# dartBoardATMEGAV1.net
KiCad netlist of a schematic drawn in EAGLE
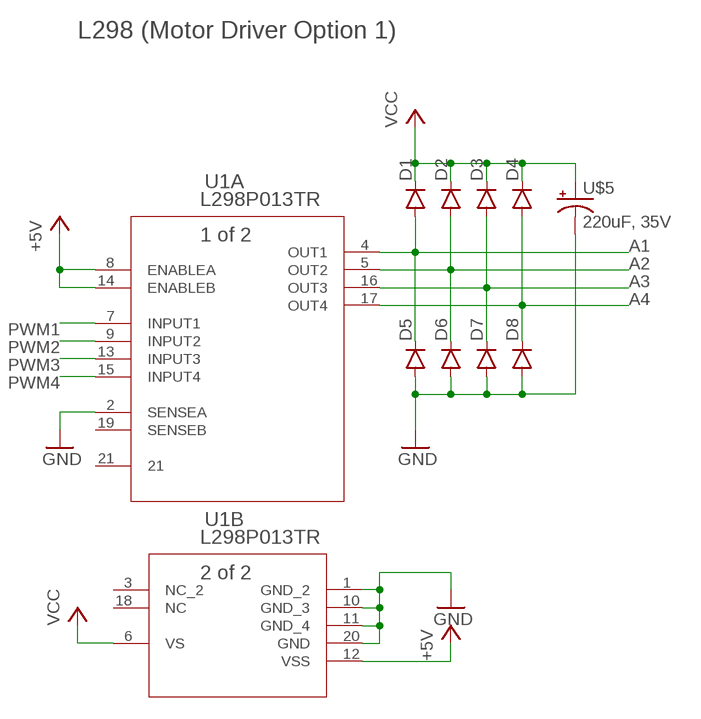
[diagram p0: schematic, sheet 1, part 1 of 2]
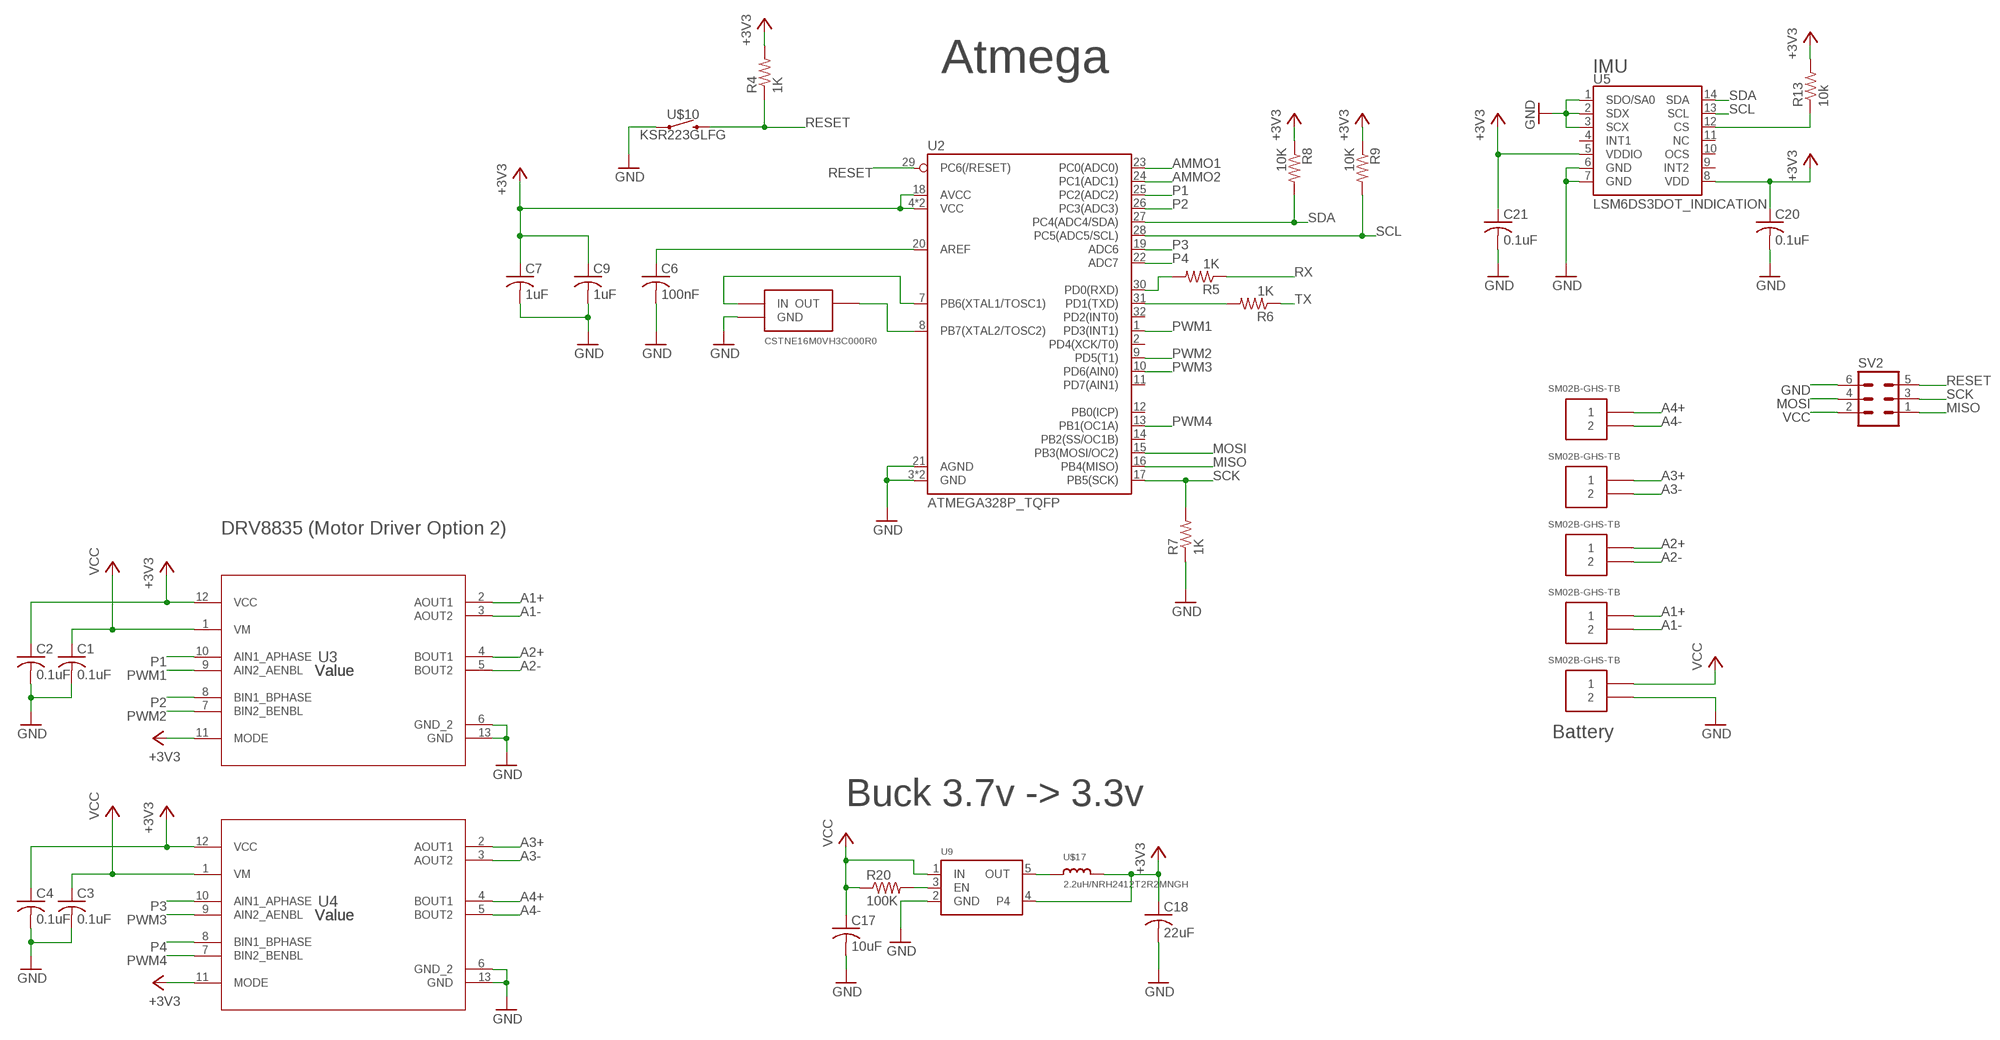
[diagram p1: schematic, sheet 1, part 2 of 2]

(export (version "E")
  (design (tool "Eeschema 10.0.6"))
  (components
    (comp (ref "C1")
      (value "0.1uF")
      (footprint "eagle-import:C0603")
      (libsource (lib "eagle-import") (part "C-USC0603"))
    )
    (comp (ref "C2")
      (value "0.1uF")
      (footprint "eagle-import:C0603")
      (libsource (lib "eagle-import") (part "C-USC0603"))
    )
    (comp (ref "C3")
      (value "0.1uF")
      (footprint "eagle-import:C0603")
      (libsource (lib "eagle-import") (part "C-USC0603"))
    )
    (comp (ref "C4")
      (value "0.1uF")
      (footprint "eagle-import:C0603")
      (libsource (lib "eagle-import") (part "C-USC0603"))
    )
    (comp (ref "C6")
      (value "100nF")
      (footprint "eagle-import:C0603")
      (libsource (lib "eagle-import") (part "C-USC0603"))
    )
    (comp (ref "C7")
      (value "1uF")
      (footprint "eagle-import:C0603")
      (libsource (lib "eagle-import") (part "C-USC0603"))
    )
    (comp (ref "C9")
      (value "1uF")
      (footprint "eagle-import:C0603")
      (libsource (lib "eagle-import") (part "C-USC0603"))
    )
    (comp (ref "C17")
      (value "10uF")
      (footprint "eagle-import:C0603")
      (libsource (lib "eagle-import") (part "C-USC0603"))
    )
    (comp (ref "C18")
      (value "22uF")
      (footprint "eagle-import:C0603")
      (libsource (lib "eagle-import") (part "C-USC0603"))
    )
    (comp (ref "C20")
      (value "0.1uF")
      (footprint "eagle-import:C0603")
      (libsource (lib "eagle-import") (part "C-USC0603"))
    )
    (comp (ref "C21")
      (value "0.1uF")
      (footprint "eagle-import:C0603")
      (libsource (lib "eagle-import") (part "C-USC0603"))
    )
    (comp (ref "D1")
      (value "DIODEDIODE-123FL")
      (footprint "eagle-import:DIODE_SOD-123FL")
      (libsource (lib "eagle-import") (part "DIODEDIODE-123FL"))
    )
    (comp (ref "D2")
      (value "DIODEDIODE-123FL")
      (footprint "eagle-import:DIODE_SOD-123FL")
      (libsource (lib "eagle-import") (part "DIODEDIODE-123FL"))
    )
    (comp (ref "D3")
      (value "DIODEDIODE-123FL")
      (footprint "eagle-import:DIODE_SOD-123FL")
      (libsource (lib "eagle-import") (part "DIODEDIODE-123FL"))
    )
    (comp (ref "D4")
      (value "DIODEDIODE-123FL")
      (footprint "eagle-import:DIODE_SOD-123FL")
      (libsource (lib "eagle-import") (part "DIODEDIODE-123FL"))
    )
    (comp (ref "D5")
      (value "DIODEDIODE-123FL")
      (footprint "eagle-import:DIODE_SOD-123FL")
      (libsource (lib "eagle-import") (part "DIODEDIODE-123FL"))
    )
    (comp (ref "D6")
      (value "DIODEDIODE-123FL")
      (footprint "eagle-import:DIODE_SOD-123FL")
      (libsource (lib "eagle-import") (part "DIODEDIODE-123FL"))
    )
    (comp (ref "D7")
      (value "DIODEDIODE-123FL")
      (footprint "eagle-import:DIODE_SOD-123FL")
      (libsource (lib "eagle-import") (part "DIODEDIODE-123FL"))
    )
    (comp (ref "D8")
      (value "DIODEDIODE-123FL")
      (footprint "eagle-import:DIODE_SOD-123FL")
      (libsource (lib "eagle-import") (part "DIODEDIODE-123FL"))
    )
    (comp (ref "R4")
      (value "1K")
      (footprint "eagle-import:R0603")
      (libsource (lib "eagle-import") (part "R-US_R0603"))
    )
    (comp (ref "R5")
      (value "1K")
      (footprint "eagle-import:R0603")
      (libsource (lib "eagle-import") (part "R-US_R0603"))
    )
    (comp (ref "R6")
      (value "1K")
      (footprint "eagle-import:R0603")
      (libsource (lib "eagle-import") (part "R-US_R0603"))
    )
    (comp (ref "R7")
      (value "1K")
      (footprint "eagle-import:R0603")
      (libsource (lib "eagle-import") (part "R-US_R0603"))
    )
    (comp (ref "R8")
      (value "10K")
      (footprint "eagle-import:R0603")
      (libsource (lib "eagle-import") (part "R-US_R0603"))
    )
    (comp (ref "R9")
      (value "10K")
      (footprint "eagle-import:R0603")
      (libsource (lib "eagle-import") (part "R-US_R0603"))
    )
    (comp (ref "R13")
      (value "10k")
      (footprint "eagle-import:R0603")
      (libsource (lib "eagle-import") (part "R-US_R0603"))
    )
    (comp (ref "R20")
      (value "100K")
      (footprint "eagle-import:R0603")
      (libsource (lib "eagle-import") (part "R-US_R0603"))
    )
    (comp (ref "SV2")
      (value "MA03-2")
      (footprint "eagle-import:MA03-2")
      (libsource (lib "eagle-import") (part "MA03-2"))
    )
    (comp (ref "U$1")
      (value "SM02B-GHS-TB")
      (footprint "eagle-import:SM02B-GHS-TB")
      (libsource (lib "eagle-import") (part "SM02B-GHS-TB"))
    )
    (comp (ref "U$2")
      (value "SM02B-GHS-TB")
      (footprint "eagle-import:SM02B-GHS-TB")
      (libsource (lib "eagle-import") (part "SM02B-GHS-TB"))
    )
    (comp (ref "U$3")
      (value "SM02B-GHS-TB")
      (footprint "eagle-import:SM02B-GHS-TB")
      (libsource (lib "eagle-import") (part "SM02B-GHS-TB"))
    )
    (comp (ref "U$4")
      (value "SM02B-GHS-TB")
      (footprint "eagle-import:SM02B-GHS-TB")
      (libsource (lib "eagle-import") (part "SM02B-GHS-TB"))
    )
    (comp (ref "U$5")
      (value "220uF, 35V")
      (footprint "eagle-import:CANCAP")
      (libsource (lib "eagle-import") (part "CANCAP"))
    )
    (comp (ref "U$7")
      (value "CSTNE16M0VH3C000R0")
      (footprint "eagle-import:CSTNE16M0VH3C000R0")
      (libsource (lib "eagle-import") (part "CSTNE16M0VH3C000R0"))
    )
    (comp (ref "U$10")
      (value "KSR223GLFG")
      (footprint "eagle-import:KSR223GLFG")
      (libsource (lib "eagle-import") (part "KSR223GLFG"))
    )
    (comp (ref "U$15")
      (value "SM02B-GHS-TB")
      (footprint "eagle-import:SM02B-GHS-TB")
      (libsource (lib "eagle-import") (part "SM02B-GHS-TB"))
    )
    (comp (ref "U$17")
      (value "2.2uH/NRH2412T2R2MNGH")
      (footprint "eagle-import:MDKK1616T2R2MM")
      (libsource (lib "eagle-import") (part "MDKK1616T2R2MM"))
    )
    (comp (ref "U1")
      (value "L298P013TR")
      (footprint "eagle-import:POWERSO-20")
      (libsource (lib "eagle-import") (part "L298P013TR"))
    )
    (comp (ref "U2")
      (value "ATMEGA328P_TQFP")
      (footprint "eagle-import:TQFP32-08")
      (libsource (lib "eagle-import") (part "ATMEGA328P_TQFP"))
    )
    (comp (ref "U3")
      (value "Value")
      (footprint "eagle-import:DSS0012A")
      (fields (field (name "MANUFACTURER") "Texas Instruments") (field (name "PARTNUMBER") "DRV8835DSSR"))
      (libsource (lib "eagle-import") (part "DRV8835DSSR"))
    )
    (comp (ref "U4")
      (value "Value")
      (footprint "eagle-import:DSS0012A")
      (fields (field (name "MANUFACTURER") "Texas Instruments") (field (name "PARTNUMBER") "DRV8835DSSR"))
      (libsource (lib "eagle-import") (part "DRV8835DSSR"))
    )
    (comp (ref "U5")
      (value "LSM6DS3DOT_INDICATION")
      (footprint "eagle-import:LGA14L_DOT_INDICATOR")
      (libsource (lib "eagle-import") (part "LSM6DS3DOT_INDICATION"))
    )
    (comp (ref "U9")
      (value "VREG_SOT23-5")
      (footprint "eagle-import:SOT23-5")
      (libsource (lib "eagle-import") (part "VREG_SOT23-5"))
    )
  )
  (nets
    (net (code "1") (name "+3V3") (class "Default")
      (node (ref "C18") (pin "1") (pinfunction "1_1") (pintype "passive"))
      (node (ref "C2") (pin "1") (pinfunction "1_1") (pintype "passive"))
      (node (ref "C20") (pin "1") (pinfunction "1_1") (pintype "passive"))
      (node (ref "C21") (pin "1") (pinfunction "1_1") (pintype "passive"))
      (node (ref "C4") (pin "1") (pinfunction "1_1") (pintype "passive"))
      (node (ref "C7") (pin "1") (pinfunction "1_1") (pintype "passive"))
      (node (ref "C9") (pin "1") (pinfunction "1_1") (pintype "passive"))
      (node (ref "R13") (pin "2") (pinfunction "2_2") (pintype "passive"))
      (node (ref "R4") (pin "2") (pinfunction "2_2") (pintype "passive"))
      (node (ref "R8") (pin "1") (pinfunction "1_1") (pintype "passive"))
      (node (ref "R9") (pin "1") (pinfunction "1_1") (pintype "passive"))
      (node (ref "U$17") (pin "P$2") (pinfunction "2_P$2") (pintype "passive"))
      (node (ref "U2") (pin "18") (pinfunction "AVCC_18") (pintype "bidirectional"))
      (node (ref "U2") (pin "4") (pinfunction "VCC_4") (pintype "bidirectional"))
      (node (ref "U2") (pin "6") (pinfunction "VCC_6") (pintype "bidirectional"))
      (node (ref "U3") (pin "11") (pinfunction "MODE_11") (pintype "input"))
      (node (ref "U3") (pin "12") (pinfunction "VCC_12") (pintype "power_in"))
      (node (ref "U4") (pin "11") (pinfunction "MODE_11") (pintype "input"))
      (node (ref "U4") (pin "12") (pinfunction "VCC_12") (pintype "power_in"))
      (node (ref "U5") (pin "5") (pinfunction "VDDIO_5") (pintype "bidirectional"))
      (node (ref "U5") (pin "8") (pinfunction "VDD_8") (pintype "bidirectional"))
      (node (ref "U9") (pin "4") (pinfunction "P4_4") (pintype "bidirectional"))
    )
    (net (code "2") (name "+5V") (class "Default")
      (node (ref "U1") (pin "12") (pinfunction "VSS_12") (pintype "power_in"))
      (node (ref "U1") (pin "14") (pinfunction "ENABLEB_14") (pintype "input"))
      (node (ref "U1") (pin "8") (pinfunction "ENABLEA_8") (pintype "input"))
    )
    (net (code "3") (name "/A1") (class "Default")
      (node (ref "D1") (pin "A") (pinfunction "A_A") (pintype "passive"))
      (node (ref "D5") (pin "C") (pinfunction "C_C") (pintype "passive"))
      (node (ref "U1") (pin "4") (pinfunction "OUT1_4") (pintype "output"))
    )
    (net (code "4") (name "/A1+") (class "Default")
      (node (ref "U$1") (pin "P$3") (pinfunction "1_P$3") (pintype "bidirectional"))
      (node (ref "U3") (pin "2") (pinfunction "AOUT1_2") (pintype "output"))
    )
    (net (code "5") (name "/A1-") (class "Default")
      (node (ref "U$1") (pin "P$4") (pinfunction "2_P$4") (pintype "bidirectional"))
      (node (ref "U3") (pin "3") (pinfunction "AOUT2_3") (pintype "output"))
    )
    (net (code "6") (name "/A2") (class "Default")
      (node (ref "D2") (pin "A") (pinfunction "A_A") (pintype "passive"))
      (node (ref "D6") (pin "C") (pinfunction "C_C") (pintype "passive"))
      (node (ref "U1") (pin "5") (pinfunction "OUT2_5") (pintype "output"))
    )
    (net (code "7") (name "/A2+") (class "Default")
      (node (ref "U$2") (pin "P$3") (pinfunction "1_P$3") (pintype "bidirectional"))
      (node (ref "U3") (pin "4") (pinfunction "BOUT1_4") (pintype "output"))
    )
    (net (code "8") (name "/A2-") (class "Default")
      (node (ref "U$2") (pin "P$4") (pinfunction "2_P$4") (pintype "bidirectional"))
      (node (ref "U3") (pin "5") (pinfunction "BOUT2_5") (pintype "output"))
    )
    (net (code "9") (name "/A3") (class "Default")
      (node (ref "D3") (pin "A") (pinfunction "A_A") (pintype "passive"))
      (node (ref "D7") (pin "C") (pinfunction "C_C") (pintype "passive"))
      (node (ref "U1") (pin "16") (pinfunction "OUT3_16") (pintype "output"))
    )
    (net (code "10") (name "/A3+") (class "Default")
      (node (ref "U$3") (pin "P$3") (pinfunction "1_P$3") (pintype "bidirectional"))
      (node (ref "U4") (pin "2") (pinfunction "AOUT1_2") (pintype "output"))
    )
    (net (code "11") (name "/A3-") (class "Default")
      (node (ref "U$3") (pin "P$4") (pinfunction "2_P$4") (pintype "bidirectional"))
      (node (ref "U4") (pin "3") (pinfunction "AOUT2_3") (pintype "output"))
    )
    (net (code "12") (name "/A4") (class "Default")
      (node (ref "D4") (pin "A") (pinfunction "A_A") (pintype "passive"))
      (node (ref "D8") (pin "C") (pinfunction "C_C") (pintype "passive"))
      (node (ref "U1") (pin "17") (pinfunction "OUT4_17") (pintype "output"))
    )
    (net (code "13") (name "/A4+") (class "Default")
      (node (ref "U$4") (pin "P$3") (pinfunction "1_P$3") (pintype "bidirectional"))
      (node (ref "U4") (pin "4") (pinfunction "BOUT1_4") (pintype "output"))
    )
    (net (code "14") (name "/A4-") (class "Default")
      (node (ref "U$4") (pin "P$4") (pinfunction "2_P$4") (pintype "bidirectional"))
      (node (ref "U4") (pin "5") (pinfunction "BOUT2_5") (pintype "output"))
    )
    (net (code "15") (name "/AMMO1") (class "Default")
      (node (ref "U2") (pin "23") (pinfunction "PC0(ADC0)_23") (pintype "bidirectional"))
    )
    (net (code "16") (name "/AMMO2") (class "Default")
      (node (ref "U2") (pin "24") (pinfunction "PC1(ADC1)_24") (pintype "bidirectional"))
    )
    (net (code "17") (name "/MISO") (class "Default")
      (node (ref "SV2") (pin "1") (pinfunction "1_1") (pintype "passive"))
      (node (ref "U2") (pin "16") (pinfunction "PB4(MISO)_16") (pintype "bidirectional"))
    )
    (net (code "18") (name "/MOSI") (class "Default")
      (node (ref "SV2") (pin "4") (pinfunction "4_4") (pintype "passive"))
      (node (ref "U2") (pin "15") (pinfunction "PB3(MOSI/OC2)_15") (pintype "bidirectional"))
    )
    (net (code "19") (name "/P1") (class "Default")
      (node (ref "U2") (pin "25") (pinfunction "PC2(ADC2)_25") (pintype "bidirectional"))
      (node (ref "U3") (pin "10") (pinfunction "AIN1_APHASE_10") (pintype "input"))
    )
    (net (code "20") (name "/P2") (class "Default")
      (node (ref "U2") (pin "26") (pinfunction "PC3(ADC3)_26") (pintype "bidirectional"))
      (node (ref "U3") (pin "8") (pinfunction "BIN1_BPHASE_8") (pintype "input"))
    )
    (net (code "21") (name "/P3") (class "Default")
      (node (ref "U2") (pin "19") (pinfunction "ADC6_19") (pintype "bidirectional"))
      (node (ref "U4") (pin "10") (pinfunction "AIN1_APHASE_10") (pintype "input"))
    )
    (net (code "22") (name "/P4") (class "Default")
      (node (ref "U2") (pin "22") (pinfunction "ADC7_22") (pintype "bidirectional"))
      (node (ref "U4") (pin "8") (pinfunction "BIN1_BPHASE_8") (pintype "input"))
    )
    (net (code "23") (name "/PWM1") (class "Default")
      (node (ref "U1") (pin "7") (pinfunction "INPUT1_7") (pintype "input"))
      (node (ref "U2") (pin "1") (pinfunction "PD3(INT1)_1") (pintype "bidirectional"))
      (node (ref "U3") (pin "9") (pinfunction "AIN2_AENBL_9") (pintype "input"))
    )
    (net (code "24") (name "/PWM2") (class "Default")
      (node (ref "U1") (pin "9") (pinfunction "INPUT2_9") (pintype "input"))
      (node (ref "U2") (pin "9") (pinfunction "PD5(T1)_9") (pintype "bidirectional"))
      (node (ref "U3") (pin "7") (pinfunction "BIN2_BENBL_7") (pintype "input"))
    )
    (net (code "25") (name "/PWM3") (class "Default")
      (node (ref "U1") (pin "13") (pinfunction "INPUT3_13") (pintype "input"))
      (node (ref "U2") (pin "10") (pinfunction "PD6(AIN0)_10") (pintype "bidirectional"))
      (node (ref "U4") (pin "9") (pinfunction "AIN2_AENBL_9") (pintype "input"))
    )
    (net (code "26") (name "/PWM4") (class "Default")
      (node (ref "U1") (pin "15") (pinfunction "INPUT4_15") (pintype "input"))
      (node (ref "U2") (pin "13") (pinfunction "PB1(OC1A)_13") (pintype "bidirectional"))
      (node (ref "U4") (pin "7") (pinfunction "BIN2_BENBL_7") (pintype "input"))
    )
    (net (code "27") (name "/RESET") (class "Default")
      (node (ref "R4") (pin "1") (pinfunction "1_1") (pintype "passive"))
      (node (ref "SV2") (pin "5") (pinfunction "5_5") (pintype "passive"))
      (node (ref "U$10") (pin "P$2") (pinfunction "2_P$2") (pintype "passive"))
      (node (ref "U2") (pin "29") (pinfunction "PC6(/RESET)_29") (pintype "bidirectional"))
    )
    (net (code "28") (name "/RX") (class "Default")
      (node (ref "R5") (pin "1") (pinfunction "1_1") (pintype "passive"))
    )
    (net (code "29") (name "/SCK") (class "Default")
      (node (ref "R7") (pin "2") (pinfunction "2_2") (pintype "passive"))
      (node (ref "SV2") (pin "3") (pinfunction "3_3") (pintype "passive"))
      (node (ref "U2") (pin "17") (pinfunction "PB5(SCK)_17") (pintype "bidirectional"))
    )
    (net (code "30") (name "/SCL") (class "Default")
      (node (ref "R9") (pin "2") (pinfunction "2_2") (pintype "passive"))
      (node (ref "U2") (pin "28") (pinfunction "PC5(ADC5/SCL)_28") (pintype "bidirectional"))
      (node (ref "U5") (pin "13") (pinfunction "SCL_13") (pintype "bidirectional"))
    )
    (net (code "31") (name "/SDA") (class "Default")
      (node (ref "R8") (pin "2") (pinfunction "2_2") (pintype "passive"))
      (node (ref "U2") (pin "27") (pinfunction "PC4(ADC4/SDA)_27") (pintype "bidirectional"))
      (node (ref "U5") (pin "14") (pinfunction "SDA_14") (pintype "bidirectional"))
    )
    (net (code "32") (name "/TX") (class "Default")
      (node (ref "R6") (pin "1") (pinfunction "1_1") (pintype "passive"))
    )
    (net (code "33") (name "GND") (class "Default")
      (node (ref "C1") (pin "2") (pinfunction "2_2") (pintype "passive"))
      (node (ref "C17") (pin "2") (pinfunction "2_2") (pintype "passive"))
      (node (ref "C18") (pin "2") (pinfunction "2_2") (pintype "passive"))
      (node (ref "C2") (pin "2") (pinfunction "2_2") (pintype "passive"))
      (node (ref "C20") (pin "2") (pinfunction "2_2") (pintype "passive"))
      (node (ref "C21") (pin "2") (pinfunction "2_2") (pintype "passive"))
      (node (ref "C3") (pin "2") (pinfunction "2_2") (pintype "passive"))
      (node (ref "C4") (pin "2") (pinfunction "2_2") (pintype "passive"))
      (node (ref "C6") (pin "2") (pinfunction "2_2") (pintype "passive"))
      (node (ref "C7") (pin "2") (pinfunction "2_2") (pintype "passive"))
      (node (ref "C9") (pin "2") (pinfunction "2_2") (pintype "passive"))
      (node (ref "D5") (pin "A") (pinfunction "A_A") (pintype "passive"))
      (node (ref "D6") (pin "A") (pinfunction "A_A") (pintype "passive"))
      (node (ref "D7") (pin "A") (pinfunction "A_A") (pintype "passive"))
      (node (ref "D8") (pin "A") (pinfunction "A_A") (pintype "passive"))
      (node (ref "R7") (pin "1") (pinfunction "1_1") (pintype "passive"))
      (node (ref "SV2") (pin "6") (pinfunction "6_6") (pintype "passive"))
      (node (ref "U$10") (pin "P$1") (pinfunction "1_P$1") (pintype "passive"))
      (node (ref "U$15") (pin "P$4") (pinfunction "2_P$4") (pintype "bidirectional"))
      (node (ref "U$5") (pin "P$1") (pinfunction "-_P$1") (pintype "passive"))
      (node (ref "U$7") (pin "2") (pinfunction "GND_2") (pintype "bidirectional"))
      (node (ref "U1") (pin "1") (pinfunction "GND_2_1") (pintype "passive"))
      (node (ref "U1") (pin "10") (pinfunction "GND_3_10") (pintype "passive"))
      (node (ref "U1") (pin "11") (pinfunction "GND_4_11") (pintype "passive"))
      (node (ref "U1") (pin "2") (pinfunction "SENSEA_2") (pintype "input"))
      (node (ref "U1") (pin "20") (pinfunction "GND_20") (pintype "passive"))
      (node (ref "U2") (pin "21") (pinfunction "AGND_21") (pintype "bidirectional"))
      (node (ref "U2") (pin "3") (pinfunction "GND_3") (pintype "bidirectional"))
      (node (ref "U2") (pin "5") (pinfunction "GND_5") (pintype "bidirectional"))
      (node (ref "U3") (pin "13") (pinfunction "GND_13") (pintype "power_in"))
      (node (ref "U3") (pin "6") (pinfunction "GND_2_6") (pintype "power_in"))
      (node (ref "U4") (pin "13") (pinfunction "GND_13") (pintype "power_in"))
      (node (ref "U4") (pin "6") (pinfunction "GND_2_6") (pintype "power_in"))
      (node (ref "U5") (pin "1") (pinfunction "SDO/SA0_1") (pintype "bidirectional"))
      (node (ref "U5") (pin "2") (pinfunction "SDX_2") (pintype "bidirectional"))
      (node (ref "U5") (pin "3") (pinfunction "SCX_3") (pintype "bidirectional"))
      (node (ref "U5") (pin "6") (pinfunction "GND_6") (pintype "bidirectional"))
      (node (ref "U5") (pin "7") (pinfunction "GND_7") (pintype "bidirectional"))
      (node (ref "U9") (pin "2") (pinfunction "GND_2") (pintype "bidirectional"))
    )
    (net (code "34") (name "Net-(U$7-IN)") (class "Default")
      (node (ref "U$7") (pin "1") (pinfunction "IN_1") (pintype "bidirectional"))
      (node (ref "U2") (pin "7") (pinfunction "PB6(XTAL1/TOSC1)_7") (pintype "bidirectional"))
    )
    (net (code "35") (name "Net-(U$7-OUT)") (class "Default")
      (node (ref "U$7") (pin "3") (pinfunction "OUT_3") (pintype "bidirectional"))
      (node (ref "U2") (pin "8") (pinfunction "PB7(XTAL2/TOSC2)_8") (pintype "bidirectional"))
    )
    (net (code "36") (name "Net-(U$17-1)") (class "Default")
      (node (ref "U$17") (pin "P$1") (pinfunction "1_P$1") (pintype "passive"))
      (node (ref "U9") (pin "5") (pinfunction "OUT_5") (pintype "bidirectional"))
    )
    (net (code "37") (name "Net-(U2-AREF)") (class "Default")
      (node (ref "C6") (pin "1") (pinfunction "1_1") (pintype "passive"))
      (node (ref "U2") (pin "20") (pinfunction "AREF_20") (pintype "bidirectional"))
    )
    (net (code "38") (name "Net-(U2-PD0(RXD))") (class "Default")
      (node (ref "R5") (pin "2") (pinfunction "2_2") (pintype "passive"))
      (node (ref "U2") (pin "30") (pinfunction "PD0(RXD)_30") (pintype "bidirectional"))
    )
    (net (code "39") (name "Net-(U2-PD1(TXD))") (class "Default")
      (node (ref "R6") (pin "2") (pinfunction "2_2") (pintype "passive"))
      (node (ref "U2") (pin "31") (pinfunction "PD1(TXD)_31") (pintype "bidirectional"))
    )
    (net (code "40") (name "Net-(U5-CS)") (class "Default")
      (node (ref "R13") (pin "1") (pinfunction "1_1") (pintype "passive"))
      (node (ref "U5") (pin "12") (pinfunction "CS_12") (pintype "bidirectional"))
    )
    (net (code "41") (name "Net-(U9-EN)") (class "Default")
      (node (ref "R20") (pin "2") (pinfunction "2_2") (pintype "passive"))
      (node (ref "U9") (pin "3") (pinfunction "EN_3") (pintype "bidirectional"))
    )
    (net (code "42") (name "VCC") (class "Default")
      (node (ref "C1") (pin "1") (pinfunction "1_1") (pintype "passive"))
      (node (ref "C17") (pin "1") (pinfunction "1_1") (pintype "passive"))
      (node (ref "C3") (pin "1") (pinfunction "1_1") (pintype "passive"))
      (node (ref "D1") (pin "C") (pinfunction "C_C") (pintype "passive"))
      (node (ref "D2") (pin "C") (pinfunction "C_C") (pintype "passive"))
      (node (ref "D3") (pin "C") (pinfunction "C_C") (pintype "passive"))
      (node (ref "D4") (pin "C") (pinfunction "C_C") (pintype "passive"))
      (node (ref "R20") (pin "1") (pinfunction "1_1") (pintype "passive"))
      (node (ref "SV2") (pin "2") (pinfunction "2_2") (pintype "passive"))
      (node (ref "U$15") (pin "P$3") (pinfunction "1_P$3") (pintype "bidirectional"))
      (node (ref "U$5") (pin "P$2") (pinfunction "+_P$2") (pintype "passive"))
      (node (ref "U1") (pin "6") (pinfunction "VS_6") (pintype "power_in"))
      (node (ref "U3") (pin "1") (pinfunction "VM_1") (pintype "power_in"))
      (node (ref "U4") (pin "1") (pinfunction "VM_1") (pintype "power_in"))
      (node (ref "U9") (pin "1") (pinfunction "IN_1") (pintype "bidirectional"))
    )
    (net (code "43") (name "unconnected-(U1-Pad21)") (class "Default")
      (node (ref "U1") (pin "21") (pinfunction "21_21") (pintype "passive"))
    )
    (net (code "44") (name "unconnected-(U1A-SENSEB-Pad19)") (class "Default")
      (node (ref "U1") (pin "19") (pinfunction "SENSEB_19") (pintype "input"))
    )
    (net (code "45") (name "unconnected-(U1B-NC-Pad18)") (class "Default")
      (node (ref "U1") (pin "18") (pinfunction "NC_18") (pintype "no_connect"))
    )
    (net (code "46") (name "unconnected-(U1B-NC_2-Pad3)") (class "Default")
      (node (ref "U1") (pin "3") (pinfunction "NC_2_3") (pintype "no_connect"))
    )
    (net (code "47") (name "unconnected-(U2-PB0(ICP)-Pad12)") (class "Default")
      (node (ref "U2") (pin "12") (pinfunction "PB0(ICP)_12") (pintype "bidirectional"))
    )
    (net (code "48") (name "unconnected-(U2-PB2(SS{slash}OC1B)-Pad14)") (class "Default")
      (node (ref "U2") (pin "14") (pinfunction "PB2(SS/OC1B)_14") (pintype "bidirectional"))
    )
    (net (code "49") (name "unconnected-(U2-PD2(INT0)-Pad32)") (class "Default")
      (node (ref "U2") (pin "32") (pinfunction "PD2(INT0)_32") (pintype "bidirectional"))
    )
    (net (code "50") (name "unconnected-(U2-PD4(XCK{slash}T0)-Pad2)") (class "Default")
      (node (ref "U2") (pin "2") (pinfunction "PD4(XCK/T0)_2") (pintype "bidirectional"))
    )
    (net (code "51") (name "unconnected-(U2-PD7(AIN1)-Pad11)") (class "Default")
      (node (ref "U2") (pin "11") (pinfunction "PD7(AIN1)_11") (pintype "bidirectional"))
    )
    (net (code "52") (name "unconnected-(U5-INT1-Pad4)") (class "Default")
      (node (ref "U5") (pin "4") (pinfunction "INT1_4") (pintype "bidirectional"))
    )
    (net (code "53") (name "unconnected-(U5-INT2-Pad9)") (class "Default")
      (node (ref "U5") (pin "9") (pinfunction "INT2_9") (pintype "bidirectional"))
    )
    (net (code "54") (name "unconnected-(U5-NC-Pad11)") (class "Default")
      (node (ref "U5") (pin "11") (pinfunction "NC_11") (pintype "bidirectional"))
    )
    (net (code "55") (name "unconnected-(U5-OCS-Pad10)") (class "Default")
      (node (ref "U5") (pin "10") (pinfunction "OCS_10") (pintype "bidirectional"))
    )
  )
)
